# Power.net
KiCad netlist of a schematic drawn in Altium Designer
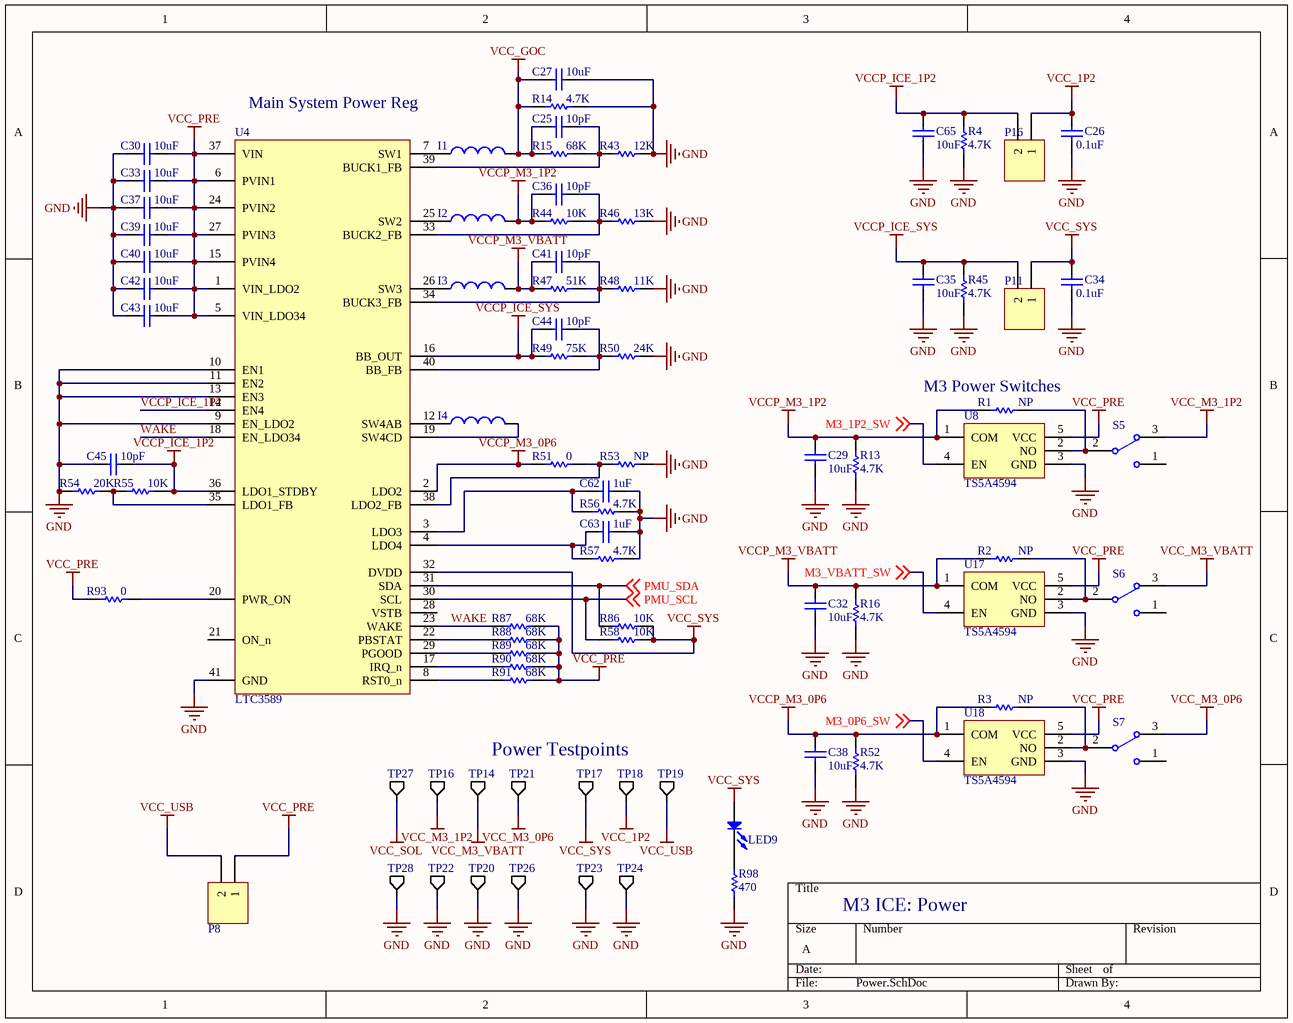
[diagram p0: Power.SchDoc]

(export (version "E")
  (design (tool "Eeschema 10.0.6"))
  (components
    (comp (ref "C25")
      (value "10pF")
      (footprint "0402")
      (description "Capacitor (Semiconductor SIM Model)")
      (fields
        (field (name "DISTPARTNO") "445-1235-1-ND")
        (field (name "MANPARTNO") "C1005C0G1H100D")
        (field (name "PUBLISHER") "Altium Limited")
      )
      (libsource (lib "Miscellaneous Devices") (part "Cap Semi"))
    )
    (comp (ref "C26")
      (value "0.1uF")
      (footprint "1608[0603]")
      (description "Capacitor (Semiconductor SIM Model)")
      (fields
        (field (name "DISTPARTNO") "1276-1005-1-ND")
        (field (name "MANPARTNO") "CL10B104KO8NNNC")
        (field (name "PUBLISHER") "Altium Limited")
      )
      (libsource (lib "Miscellaneous Devices") (part "Cap Semi"))
    )
    (comp (ref "C27")
      (value "10uF")
      (footprint "0805")
      (description "Capacitor (Semiconductor SIM Model)")
      (fields
        (field (name "DISTPARTNO") "445-6857-1-ND")
        (field (name "MANPARTNO") "C2012X7R1A106K")
        (field (name "PUBLISHER") "Altium Limited")
      )
      (libsource (lib "M3") (part "Cap Chip"))
    )
    (comp (ref "C29")
      (value "10uF")
      (footprint "0805")
      (description "Capacitor (Semiconductor SIM Model)")
      (fields
        (field (name "DISTPARTNO") "445-6857-1-ND")
        (field (name "MANPARTNO") "C2012X7R1A106K")
        (field (name "PUBLISHER") "Altium Limited")
      )
      (libsource (lib "M3") (part "Cap Chip"))
    )
    (comp (ref "C30")
      (value "10uF")
      (footprint "0805")
      (description "Capacitor (Semiconductor SIM Model)")
      (fields
        (field (name "DISTPARTNO") "445-6857-1-ND")
        (field (name "MANPARTNO") "C2012X7R1A106K")
        (field (name "PUBLISHER") "Altium Limited")
      )
      (libsource (lib "M3") (part "Cap Chip"))
    )
    (comp (ref "C32")
      (value "10uF")
      (footprint "0805")
      (description "Capacitor (Semiconductor SIM Model)")
      (fields
        (field (name "DISTPARTNO") "445-6857-1-ND")
        (field (name "MANPARTNO") "C2012X7R1A106K")
        (field (name "PUBLISHER") "Altium Limited")
      )
      (libsource (lib "M3") (part "Cap Chip"))
    )
    (comp (ref "C33")
      (value "10uF")
      (footprint "0805")
      (description "Capacitor (Semiconductor SIM Model)")
      (fields
        (field (name "DISTPARTNO") "445-6857-1-ND")
        (field (name "MANPARTNO") "C2012X7R1A106K")
        (field (name "PUBLISHER") "Altium Limited")
      )
      (libsource (lib "M3") (part "Cap Chip"))
    )
    (comp (ref "C34")
      (value "0.1uF")
      (footprint "1608[0603]")
      (description "Capacitor (Semiconductor SIM Model)")
      (fields
        (field (name "DISTPARTNO") "1276-1005-1-ND")
        (field (name "MANPARTNO") "CL10B104KO8NNNC")
        (field (name "PUBLISHER") "Altium Limited")
      )
      (libsource (lib "Miscellaneous Devices") (part "Cap Semi"))
    )
    (comp (ref "C35")
      (value "10uF")
      (footprint "0805")
      (description "Capacitor (Semiconductor SIM Model)")
      (fields
        (field (name "DISTPARTNO") "445-6857-1-ND")
        (field (name "MANPARTNO") "C2012X7R1A106K")
        (field (name "PUBLISHER") "Altium Limited")
      )
      (libsource (lib "M3") (part "Cap Chip"))
    )
    (comp (ref "C36")
      (value "10pF")
      (footprint "0402")
      (description "Capacitor (Semiconductor SIM Model)")
      (fields
        (field (name "DISTPARTNO") "445-1235-1-ND")
        (field (name "MANPARTNO") "C1005C0G1H100D")
        (field (name "PUBLISHER") "Altium Limited")
      )
      (libsource (lib "Miscellaneous Devices") (part "Cap Semi"))
    )
    (comp (ref "C37")
      (value "10uF")
      (footprint "0805")
      (description "Capacitor (Semiconductor SIM Model)")
      (fields
        (field (name "DISTPARTNO") "445-6857-1-ND")
        (field (name "MANPARTNO") "C2012X7R1A106K")
        (field (name "PUBLISHER") "Altium Limited")
      )
      (libsource (lib "M3") (part "Cap Chip"))
    )
    (comp (ref "C38")
      (value "10uF")
      (footprint "0805")
      (description "Capacitor (Semiconductor SIM Model)")
      (fields
        (field (name "DISTPARTNO") "445-6857-1-ND")
        (field (name "MANPARTNO") "C2012X7R1A106K")
        (field (name "PUBLISHER") "Altium Limited")
      )
      (libsource (lib "M3") (part "Cap Chip"))
    )
    (comp (ref "C39")
      (value "10uF")
      (footprint "0805")
      (description "Capacitor (Semiconductor SIM Model)")
      (fields
        (field (name "DISTPARTNO") "445-6857-1-ND")
        (field (name "MANPARTNO") "C2012X7R1A106K")
        (field (name "PUBLISHER") "Altium Limited")
      )
      (libsource (lib "M3") (part "Cap Chip"))
    )
    (comp (ref "C40")
      (value "10uF")
      (footprint "0805")
      (description "Capacitor (Semiconductor SIM Model)")
      (fields
        (field (name "DISTPARTNO") "445-6857-1-ND")
        (field (name "MANPARTNO") "C2012X7R1A106K")
        (field (name "PUBLISHER") "Altium Limited")
      )
      (libsource (lib "M3") (part "Cap Chip"))
    )
    (comp (ref "C41")
      (value "10pF")
      (footprint "0402")
      (description "Capacitor (Semiconductor SIM Model)")
      (fields
        (field (name "DISTPARTNO") "445-1235-1-ND")
        (field (name "MANPARTNO") "C1005C0G1H100D")
        (field (name "PUBLISHER") "Altium Limited")
      )
      (libsource (lib "Miscellaneous Devices") (part "Cap Semi"))
    )
    (comp (ref "C42")
      (value "10uF")
      (footprint "0805")
      (description "Capacitor (Semiconductor SIM Model)")
      (fields
        (field (name "DISTPARTNO") "445-6857-1-ND")
        (field (name "MANPARTNO") "C2012X7R1A106K")
        (field (name "PUBLISHER") "Altium Limited")
      )
      (libsource (lib "M3") (part "Cap Chip"))
    )
    (comp (ref "C43")
      (value "10uF")
      (footprint "0805")
      (description "Capacitor (Semiconductor SIM Model)")
      (fields
        (field (name "DISTPARTNO") "445-6857-1-ND")
        (field (name "MANPARTNO") "C2012X7R1A106K")
        (field (name "PUBLISHER") "Altium Limited")
      )
      (libsource (lib "M3") (part "Cap Chip"))
    )
    (comp (ref "C44")
      (value "10pF")
      (footprint "0402")
      (description "Capacitor (Semiconductor SIM Model)")
      (fields
        (field (name "DISTPARTNO") "445-1235-1-ND")
        (field (name "MANPARTNO") "C1005C0G1H100D")
        (field (name "PUBLISHER") "Altium Limited")
      )
      (libsource (lib "Miscellaneous Devices") (part "Cap Semi"))
    )
    (comp (ref "C45")
      (value "10pF")
      (footprint "0402")
      (description "Capacitor (Semiconductor SIM Model)")
      (fields
        (field (name "DISTPARTNO") "445-1235-1-ND")
        (field (name "MANPARTNO") "C1005C0G1H100D")
        (field (name "PUBLISHER") "Altium Limited")
      )
      (libsource (lib "Miscellaneous Devices") (part "Cap Semi"))
    )
    (comp (ref "C62")
      (value "1uF")
      (footprint "0402")
      (description "Capacitor (Semiconductor SIM Model)")
      (fields
        (field (name "DISTPARTNO") "445-4991-1-ND")
        (field (name "MANPARTNO") "C1005X5R1A105M")
        (field (name "PUBLISHER") "Altium Limited")
      )
      (libsource (lib "Miscellaneous Devices") (part "Cap Semi"))
    )
    (comp (ref "C63")
      (value "1uF")
      (footprint "0402")
      (description "Capacitor (Semiconductor SIM Model)")
      (fields
        (field (name "DISTPARTNO") "445-4991-1-ND")
        (field (name "MANPARTNO") "C1005X5R1A105M")
        (field (name "PUBLISHER") "Altium Limited")
      )
      (libsource (lib "Miscellaneous Devices") (part "Cap Semi"))
    )
    (comp (ref "C65")
      (value "10uF")
      (footprint "0805")
      (description "Capacitor (Semiconductor SIM Model)")
      (fields
        (field (name "DISTPARTNO") "445-6857-1-ND")
        (field (name "MANPARTNO") "C2012X7R1A106K")
        (field (name "PUBLISHER") "Altium Limited")
      )
      (libsource (lib "M3") (part "Cap Chip"))
    )
    (comp (ref "I1")
      (value "NR5040T1R5N")
      (footprint "INDUCTOR_.118x.142mm")
      (fields (field (name "DISTPARTNO") "541-1327-1-ND") (field (name "MANPARTNO") "IHLP1212AEER1R0M11"))
      (libsource (lib "M3") (part "IHLP1212"))
    )
    (comp (ref "I2")
      (value "NR5040T1R5N")
      (footprint "INDUCTOR_.118x.142mm")
      (fields (field (name "DISTPARTNO") "541-1327-1-ND") (field (name "MANPARTNO") "IHLP1212AEER1R0M11"))
      (libsource (lib "M3") (part "IHLP1212"))
    )
    (comp (ref "I3")
      (value "NR5040T1R5N")
      (footprint "INDUCTOR_.118x.142mm")
      (fields (field (name "DISTPARTNO") "541-1327-1-ND") (field (name "MANPARTNO") "IHLP1212AEER1R0M11"))
      (libsource (lib "M3") (part "IHLP1212"))
    )
    (comp (ref "I4")
      (value "NR5040T1R5N")
      (footprint "INDUCTOR_.118x.142mm")
      (fields (field (name "DISTPARTNO") "541-1327-1-ND") (field (name "MANPARTNO") "IHLP1212AEER1R0M11"))
      (libsource (lib "M3") (part "IHLP1212"))
    )
    (comp (ref "LED9")
      (value "LED 1206")
      (footprint "1206_LED")
      (fields (field (name "DISTPARTNO") "160-1169-1-ND") (field (name "MANPARTNO") "LTST-C150GKT"))
      (libsource (lib "M3") (part "LED 1206"))
    )
    (comp (ref "P8")
      (value "Header 2")
      (footprint "HDR1X2")
      (description "Header, 2-Pin")
      (fields
        (field (name "DISTPARTNO") "A26514-02-ND")
        (field (name "MANPARTNO") "4-103327-0-02")
        (field (name "PUBLISHER") "Altium Limited")
      )
      (libsource (lib "Miscellaneous Connectors") (part "Header 2"))
    )
    (comp (ref "P11")
      (value "Header 2")
      (footprint "HDR1X2")
      (description "Header, 2-Pin")
      (fields
        (field (name "DISTPARTNO") "A26514-02-ND")
        (field (name "MANPARTNO") "4-103327-0-02")
        (field (name "PUBLISHER") "Altium Limited")
      )
      (libsource (lib "Miscellaneous Connectors") (part "Header 2"))
    )
    (comp (ref "P16")
      (value "Header 2")
      (footprint "HDR1X2")
      (description "Header, 2-Pin")
      (fields
        (field (name "DISTPARTNO") "A26514-02-ND")
        (field (name "MANPARTNO") "4-103327-0-02")
        (field (name "PUBLISHER") "Altium Limited")
      )
      (libsource (lib "Miscellaneous Connectors") (part "Header 2"))
    )
    (comp (ref "R1")
      (value "NP")
      (footprint "0603")
      (description "Semiconductor Resistor")
      (fields (field (name "Comment") "Res Chip") (field (name "PUBLISHER") "Altium Limited"))
      (libsource (lib "M3") (part "Res Chip"))
    )
    (comp (ref "R2")
      (value "NP")
      (footprint "0603")
      (description "Semiconductor Resistor")
      (fields (field (name "Comment") "Res Chip") (field (name "PUBLISHER") "Altium Limited"))
      (libsource (lib "M3") (part "Res Chip"))
    )
    (comp (ref "R3")
      (value "NP")
      (footprint "0603")
      (description "Semiconductor Resistor")
      (fields (field (name "Comment") "Res Chip") (field (name "PUBLISHER") "Altium Limited"))
      (libsource (lib "M3") (part "Res Chip"))
    )
    (comp (ref "R4")
      (value "4.7K")
      (footprint "0603")
      (description "Semiconductor Resistor")
      (fields
        (field (name "DISTPARTNO") "P4.7KGCT-ND")
        (field (name "MANPARTNO") "ERJ-3GEYJ472V")
        (field (name "PUBLISHER") "Altium Limited")
      )
      (libsource (lib "M3") (part "Res Chip"))
    )
    (comp (ref "R13")
      (value "4.7K")
      (footprint "0603")
      (description "Semiconductor Resistor")
      (fields
        (field (name "DISTPARTNO") "P4.7KGCT-ND")
        (field (name "MANPARTNO") "ERJ-3GEYJ472V")
        (field (name "PUBLISHER") "Altium Limited")
      )
      (libsource (lib "M3") (part "Res Chip"))
    )
    (comp (ref "R14")
      (value "4.7K")
      (footprint "0603")
      (description "Semiconductor Resistor")
      (fields
        (field (name "DISTPARTNO") "P4.7KGCT-ND")
        (field (name "MANPARTNO") "ERJ-3GEYJ472V")
        (field (name "PUBLISHER") "Altium Limited")
      )
      (libsource (lib "M3") (part "Res Chip"))
    )
    (comp (ref "R15")
      (value "68K")
      (footprint "0402")
      (description "Semiconductor Resistor")
      (fields
        (field (name "DISTPARTNO") "P68.0KLCT-ND")
        (field (name "MANPARTNO") "ERJ-2RKF6802X")
        (field (name "PUBLISHER") "Altium Limited")
      )
      (libsource (lib "M3") (part "Res Chip"))
    )
    (comp (ref "R16")
      (value "4.7K")
      (footprint "0603")
      (description "Semiconductor Resistor")
      (fields
        (field (name "DISTPARTNO") "P4.7KGCT-ND")
        (field (name "MANPARTNO") "ERJ-3GEYJ472V")
        (field (name "PUBLISHER") "Altium Limited")
      )
      (libsource (lib "M3") (part "Res Chip"))
    )
    (comp (ref "R43")
      (value "12K")
      (footprint "0402")
      (description "Semiconductor Resistor")
      (fields
        (field (name "DISTPARTNO") "P12.0KLCT-ND")
        (field (name "MANPARTNO") "ERJ-2RKF1202X")
        (field (name "PUBLISHER") "Altium Limited")
      )
      (libsource (lib "M3") (part "Res Chip"))
    )
    (comp (ref "R44")
      (value "10K")
      (footprint "0402")
      (description "Semiconductor Resistor")
      (fields
        (field (name "DISTPARTNO") "P10.0KLCT-ND")
        (field (name "MANPARTNO") "ERJ-2RKF1002X")
        (field (name "PUBLISHER") "Altium Limited")
      )
      (libsource (lib "M3") (part "Res Chip"))
    )
    (comp (ref "R45")
      (value "4.7K")
      (footprint "0603")
      (description "Semiconductor Resistor")
      (fields
        (field (name "DISTPARTNO") "P4.7KGCT-ND")
        (field (name "MANPARTNO") "ERJ-3GEYJ472V")
        (field (name "PUBLISHER") "Altium Limited")
      )
      (libsource (lib "M3") (part "Res Chip"))
    )
    (comp (ref "R46")
      (value "13K")
      (footprint "0402")
      (description "Semiconductor Resistor")
      (fields
        (field (name "DISTPARTNO") "311-13.0KLRCT-ND")
        (field (name "MANPARTNO") "RC0402FR-0713KL")
        (field (name "PUBLISHER") "Altium Limited")
      )
      (libsource (lib "M3") (part "Res Chip"))
    )
    (comp (ref "R47")
      (value "51K")
      (footprint "0402")
      (description "Semiconductor Resistor")
      (fields
        (field (name "DISTPARTNO") "P51.0KLCT-ND")
        (field (name "MANPARTNO") "ERJ-2RKF5102X")
        (field (name "PUBLISHER") "Altium Limited")
      )
      (libsource (lib "M3") (part "Res Chip"))
    )
    (comp (ref "R48")
      (value "11K")
      (footprint "0402")
      (description "Semiconductor Resistor")
      (fields
        (field (name "DISTPARTNO") "P11.0KLCT-ND")
        (field (name "MANPARTNO") "ERJ-2RKF1102X")
        (field (name "PUBLISHER") "Altium Limited")
      )
      (libsource (lib "M3") (part "Res Chip"))
    )
    (comp (ref "R49")
      (value "75K")
      (footprint "0402")
      (description "Semiconductor Resistor")
      (fields
        (field (name "DISTPARTNO") "P75.0KLCT-ND")
        (field (name "MANPARTNO") "ERJ-2RKF7502X")
        (field (name "PUBLISHER") "Altium Limited")
      )
      (libsource (lib "M3") (part "Res Chip"))
    )
    (comp (ref "R50")
      (value "24K")
      (footprint "0402")
      (description "Semiconductor Resistor")
      (fields
        (field (name "DISTPARTNO") "RMCF0402FT24K0CT-ND")
        (field (name "MANPARTNO") "RMCF0402FT24K0")
        (field (name "PUBLISHER") "Altium Limited")
      )
      (libsource (lib "M3") (part "Res Chip"))
    )
    (comp (ref "R51")
      (value "0")
      (footprint "0402")
      (description "Semiconductor Resistor")
      (fields
        (field (name "DISTPARTNO") "P0.0JCT-ND")
        (field (name "MANPARTNO") "ERJ-2GE0R00X")
        (field (name "PUBLISHER") "Altium Limited")
      )
      (libsource (lib "M3") (part "Res Chip"))
    )
    (comp (ref "R52")
      (value "4.7K")
      (footprint "0603")
      (description "Semiconductor Resistor")
      (fields
        (field (name "DISTPARTNO") "P4.7KGCT-ND")
        (field (name "MANPARTNO") "ERJ-3GEYJ472V")
        (field (name "PUBLISHER") "Altium Limited")
      )
      (libsource (lib "M3") (part "Res Chip"))
    )
    (comp (ref "R53")
      (value "NP")
      (footprint "0402")
      (description "Semiconductor Resistor")
      (fields (field (name "Comment") "Res Chip") (field (name "PUBLISHER") "Altium Limited"))
      (libsource (lib "M3") (part "Res Chip"))
    )
    (comp (ref "R54")
      (value "20K")
      (footprint "0402")
      (description "Semiconductor Resistor")
      (fields
        (field (name "DISTPARTNO") "P20.0KLCT-ND")
        (field (name "MANPARTNO") "ERJ-2RKF2002X")
        (field (name "PUBLISHER") "Altium Limited")
      )
      (libsource (lib "M3") (part "Res Chip"))
    )
    (comp (ref "R55")
      (value "10K")
      (footprint "0402")
      (description "Semiconductor Resistor")
      (fields
        (field (name "DISTPARTNO") "P10.0KLCT-ND")
        (field (name "MANPARTNO") "ERJ-2RKF1002X")
        (field (name "PUBLISHER") "Altium Limited")
      )
      (libsource (lib "M3") (part "Res Chip"))
    )
    (comp (ref "R56")
      (value "4.7K")
      (footprint "0402")
      (description "Semiconductor Resistor")
      (fields
        (field (name "DISTPARTNO") "P4.70KLCT-ND")
        (field (name "MANPARTNO") "ERJ-2RKF4701X")
        (field (name "PUBLISHER") "Altium Limited")
      )
      (libsource (lib "M3") (part "Res Chip"))
    )
    (comp (ref "R57")
      (value "4.7K")
      (footprint "0402")
      (description "Semiconductor Resistor")
      (fields
        (field (name "DISTPARTNO") "P4.70KLCT-ND")
        (field (name "MANPARTNO") "ERJ-2RKF4701X")
        (field (name "PUBLISHER") "Altium Limited")
      )
      (libsource (lib "M3") (part "Res Chip"))
    )
    (comp (ref "R58")
      (value "10K")
      (footprint "0402")
      (description "Semiconductor Resistor")
      (fields
        (field (name "DISTPARTNO") "P10.0KLCT-ND")
        (field (name "MANPARTNO") "ERJ-2RKF1002X")
        (field (name "PUBLISHER") "Altium Limited")
      )
      (libsource (lib "M3") (part "Res Chip"))
    )
    (comp (ref "R86")
      (value "10K")
      (footprint "0402")
      (description "Semiconductor Resistor")
      (fields
        (field (name "DISTPARTNO") "P10.0KLCT-ND")
        (field (name "MANPARTNO") "ERJ-2RKF1002X")
        (field (name "PUBLISHER") "Altium Limited")
      )
      (libsource (lib "M3") (part "Res Chip"))
    )
    (comp (ref "R87")
      (value "68K")
      (footprint "0402")
      (description "Semiconductor Resistor")
      (fields
        (field (name "DISTPARTNO") "P68.0KLCT-ND")
        (field (name "MANPARTNO") "ERJ-2RKF6802X")
        (field (name "PUBLISHER") "Altium Limited")
      )
      (libsource (lib "M3") (part "Res Chip"))
    )
    (comp (ref "R88")
      (value "68K")
      (footprint "0402")
      (description "Semiconductor Resistor")
      (fields
        (field (name "DISTPARTNO") "P68.0KLCT-ND")
        (field (name "MANPARTNO") "ERJ-2RKF6802X")
        (field (name "PUBLISHER") "Altium Limited")
      )
      (libsource (lib "M3") (part "Res Chip"))
    )
    (comp (ref "R89")
      (value "68K")
      (footprint "0402")
      (description "Semiconductor Resistor")
      (fields
        (field (name "DISTPARTNO") "P68.0KLCT-ND")
        (field (name "MANPARTNO") "ERJ-2RKF6802X")
        (field (name "PUBLISHER") "Altium Limited")
      )
      (libsource (lib "M3") (part "Res Chip"))
    )
    (comp (ref "R90")
      (value "68K")
      (footprint "0402")
      (description "Semiconductor Resistor")
      (fields
        (field (name "DISTPARTNO") "P68.0KLCT-ND")
        (field (name "MANPARTNO") "ERJ-2RKF6802X")
        (field (name "PUBLISHER") "Altium Limited")
      )
      (libsource (lib "M3") (part "Res Chip"))
    )
    (comp (ref "R91")
      (value "68K")
      (footprint "0402")
      (description "Semiconductor Resistor")
      (fields
        (field (name "DISTPARTNO") "P68.0KLCT-ND")
        (field (name "MANPARTNO") "ERJ-2RKF6802X")
        (field (name "PUBLISHER") "Altium Limited")
      )
      (libsource (lib "M3") (part "Res Chip"))
    )
    (comp (ref "R93")
      (value "0")
      (footprint "0402")
      (description "Semiconductor Resistor")
      (fields
        (field (name "DISTPARTNO") "P0.0JCT-ND")
        (field (name "MANPARTNO") "ERJ-2GE0R00X")
        (field (name "PUBLISHER") "Altium Limited")
      )
      (libsource (lib "M3") (part "Res Chip"))
    )
    (comp (ref "R98")
      (value "470")
      (footprint "0603")
      (description "Semiconductor Resistor")
      (fields
        (field (name "DISTPARTNO") "P470GCT-ND")
        (field (name "MANPARTNO") "ERJ-3GEYJ471V")
        (field (name "PUBLISHER") "Altium Limited")
      )
      (libsource (lib "M3") (part "Res Chip"))
    )
    (comp (ref "S5")
      (value "OS102011MS2QN1")
      (footprint "SPDT_SW2")
      (description "SPDT Slide Switch")
      (fields (field (name "DISTPARTNO") "CKN9565-ND"))
      (libsource (lib "M3") (part "OS102011MS2QN1"))
    )
    (comp (ref "S6")
      (value "OS102011MS2QN1")
      (footprint "SPDT_SW2")
      (description "SPDT Slide Switch")
      (fields (field (name "DISTPARTNO") "CKN9565-ND"))
      (libsource (lib "M3") (part "OS102011MS2QN1"))
    )
    (comp (ref "S7")
      (value "OS102011MS2QN1")
      (footprint "SPDT_SW2")
      (description "SPDT Slide Switch")
      (fields (field (name "DISTPARTNO") "CKN9565-ND"))
      (libsource (lib "M3") (part "OS102011MS2QN1"))
    )
    (comp (ref "TP14") (value "TP") (footprint "TP") (libsource (lib "M3") (part "TP")))
    (comp (ref "TP16") (value "TP") (footprint "TP") (libsource (lib "M3") (part "TP")))
    (comp (ref "TP17") (value "TP") (footprint "TP") (libsource (lib "M3") (part "TP")))
    (comp (ref "TP18") (value "TP") (footprint "TP") (libsource (lib "M3") (part "TP")))
    (comp (ref "TP19") (value "TP") (footprint "TP") (libsource (lib "M3") (part "TP")))
    (comp (ref "TP20") (value "TP") (footprint "TP") (libsource (lib "M3") (part "TP")))
    (comp (ref "TP21") (value "TP") (footprint "TP") (libsource (lib "M3") (part "TP")))
    (comp (ref "TP22") (value "TP") (footprint "TP") (libsource (lib "M3") (part "TP")))
    (comp (ref "TP23") (value "TP") (footprint "TP") (libsource (lib "M3") (part "TP")))
    (comp (ref "TP24") (value "TP") (footprint "TP") (libsource (lib "M3") (part "TP")))
    (comp (ref "TP26") (value "TP") (footprint "TP") (libsource (lib "M3") (part "TP")))
    (comp (ref "TP27") (value "TP") (footprint "TP") (libsource (lib "M3") (part "TP")))
    (comp (ref "TP28") (value "TP") (footprint "TP") (libsource (lib "M3") (part "TP")))
    (comp (ref "U4")
      (value "LTC3589")
      (footprint "QFN-40")
      (fields (field (name "DISTPARTNO") "LTC3589EUJ-2#PBF-ND") (field (name "MANPARTNO") "LTC3589EUJ-2#PBF"))
      (libsource (lib "M3") (part "LTC3589"))
    )
    (comp (ref "U8")
      (value "TS5A4594")
      (footprint "SOT25")
      (description "SPST Analog Switch")
      (fields (field (name "DISTPARTNO") "296-17705-1-ND") (field (name "MANPARTNO") "TS5A4594DBVR"))
      (libsource (lib "M3") (part "TS5A4594"))
    )
    (comp (ref "U17")
      (value "TS5A4594")
      (footprint "SOT25")
      (description "SPST Analog Switch")
      (fields (field (name "DISTPARTNO") "296-17705-1-ND") (field (name "MANPARTNO") "TS5A4594DBVR"))
      (libsource (lib "M3") (part "TS5A4594"))
    )
    (comp (ref "U18")
      (value "TS5A4594")
      (footprint "SOT25")
      (description "SPST Analog Switch")
      (fields (field (name "DISTPARTNO") "296-17705-1-ND") (field (name "MANPARTNO") "TS5A4594DBVR"))
      (libsource (lib "M3") (part "TS5A4594"))
    )
  )
  (nets
    (net (code "1") (name "/WAKE") (class "Default")
      (node (ref "R87") (pin "1") (pinfunction "1_1") (pintype "passive"))
      (node (ref "U4") (pin "18") (pinfunction "EN_LDO34_18") (pintype "passive"))
      (node (ref "U4") (pin "23") (pinfunction "WAKE_23") (pintype "passive"))
    )
    (net (code "2") (name "GND") (class "Default")
      (node (ref "C26") (pin "1") (pinfunction "1_1") (pintype "passive"))
      (node (ref "C27") (pin "1") (pinfunction "1_1") (pintype "passive"))
      (node (ref "C29") (pin "1") (pinfunction "1_1") (pintype "passive"))
      (node (ref "C30") (pin "2") (pinfunction "2_2") (pintype "passive"))
      (node (ref "C32") (pin "1") (pinfunction "1_1") (pintype "passive"))
      (node (ref "C33") (pin "2") (pinfunction "2_2") (pintype "passive"))
      (node (ref "C34") (pin "1") (pinfunction "1_1") (pintype "passive"))
      (node (ref "C35") (pin "1") (pinfunction "1_1") (pintype "passive"))
      (node (ref "C37") (pin "2") (pinfunction "2_2") (pintype "passive"))
      (node (ref "C38") (pin "1") (pinfunction "1_1") (pintype "passive"))
      (node (ref "C39") (pin "2") (pinfunction "2_2") (pintype "passive"))
      (node (ref "C40") (pin "2") (pinfunction "2_2") (pintype "passive"))
      (node (ref "C42") (pin "2") (pinfunction "2_2") (pintype "passive"))
      (node (ref "C43") (pin "2") (pinfunction "2_2") (pintype "passive"))
      (node (ref "C45") (pin "2") (pinfunction "2_2") (pintype "passive"))
      (node (ref "C62") (pin "1") (pinfunction "1_1") (pintype "passive"))
      (node (ref "C63") (pin "1") (pinfunction "1_1") (pintype "passive"))
      (node (ref "C65") (pin "2") (pinfunction "2_2") (pintype "passive"))
      (node (ref "R13") (pin "1") (pinfunction "1_1") (pintype "passive"))
      (node (ref "R14") (pin "1") (pinfunction "1_1") (pintype "passive"))
      (node (ref "R16") (pin "1") (pinfunction "1_1") (pintype "passive"))
      (node (ref "R4") (pin "2") (pinfunction "2_2") (pintype "passive"))
      (node (ref "R43") (pin "2") (pinfunction "2_2") (pintype "passive"))
      (node (ref "R45") (pin "1") (pinfunction "1_1") (pintype "passive"))
      (node (ref "R46") (pin "2") (pinfunction "2_2") (pintype "passive"))
      (node (ref "R48") (pin "2") (pinfunction "2_2") (pintype "passive"))
      (node (ref "R50") (pin "2") (pinfunction "2_2") (pintype "passive"))
      (node (ref "R52") (pin "1") (pinfunction "1_1") (pintype "passive"))
      (node (ref "R53") (pin "2") (pinfunction "2_2") (pintype "passive"))
      (node (ref "R54") (pin "1") (pinfunction "1_1") (pintype "passive"))
      (node (ref "R56") (pin "2") (pinfunction "2_2") (pintype "passive"))
      (node (ref "R57") (pin "2") (pinfunction "2_2") (pintype "passive"))
      (node (ref "R98") (pin "1") (pinfunction "1_1") (pintype "passive"))
      (node (ref "TP20") (pin "1") (pinfunction "A_1") (pintype "passive"))
      (node (ref "TP22") (pin "1") (pinfunction "A_1") (pintype "passive"))
      (node (ref "TP23") (pin "1") (pinfunction "A_1") (pintype "passive"))
      (node (ref "TP24") (pin "1") (pinfunction "A_1") (pintype "passive"))
      (node (ref "TP26") (pin "1") (pinfunction "A_1") (pintype "passive"))
      (node (ref "TP28") (pin "1") (pinfunction "A_1") (pintype "passive"))
      (node (ref "U17") (pin "3") (pinfunction "GND_3") (pintype "passive"))
      (node (ref "U18") (pin "3") (pinfunction "GND_3") (pintype "passive"))
      (node (ref "U4") (pin "10") (pinfunction "EN1_10") (pintype "passive"))
      (node (ref "U4") (pin "11") (pinfunction "EN2_11") (pintype "passive"))
      (node (ref "U4") (pin "13") (pinfunction "EN3_13") (pintype "passive"))
      (node (ref "U4") (pin "41") (pinfunction "GND_41") (pintype "passive"))
      (node (ref "U4") (pin "9") (pinfunction "EN_LDO2_9") (pintype "passive"))
      (node (ref "U8") (pin "3") (pinfunction "GND_3") (pintype "passive"))
    )
    (net (code "3") (name "M3_0P6_SW") (class "Default")
      (node (ref "U18") (pin "4") (pinfunction "EN_4") (pintype "passive"))
    )
    (net (code "4") (name "M3_1P2_SW") (class "Default")
      (node (ref "U8") (pin "4") (pinfunction "EN_4") (pintype "passive"))
    )
    (net (code "5") (name "M3_VBATT_SW") (class "Default")
      (node (ref "U17") (pin "4") (pinfunction "EN_4") (pintype "passive"))
    )
    (net (code "6") (name "Net-(LED9-K)") (class "Default")
      (node (ref "LED9") (pin "2") (pinfunction "K_2") (pintype "passive"))
      (node (ref "R98") (pin "2") (pinfunction "2_2") (pintype "passive"))
    )
    (net (code "7") (name "Net-(U4-BB_FB)") (class "Default")
      (node (ref "C44") (pin "1") (pinfunction "1_1") (pintype "passive"))
      (node (ref "R49") (pin "2") (pinfunction "2_2") (pintype "passive"))
      (node (ref "R50") (pin "1") (pinfunction "1_1") (pintype "passive"))
      (node (ref "U4") (pin "40") (pinfunction "BB_FB_40") (pintype "passive"))
    )
    (net (code "8") (name "Net-(U4-BUCK1_FB)") (class "Default")
      (node (ref "C25") (pin "1") (pinfunction "1_1") (pintype "passive"))
      (node (ref "R15") (pin "2") (pinfunction "2_2") (pintype "passive"))
      (node (ref "R43") (pin "1") (pinfunction "1_1") (pintype "passive"))
      (node (ref "U4") (pin "39") (pinfunction "BUCK1_FB_39") (pintype "passive"))
    )
    (net (code "9") (name "Net-(U4-BUCK2_FB)") (class "Default")
      (node (ref "C36") (pin "1") (pinfunction "1_1") (pintype "passive"))
      (node (ref "R44") (pin "2") (pinfunction "2_2") (pintype "passive"))
      (node (ref "R46") (pin "1") (pinfunction "1_1") (pintype "passive"))
      (node (ref "U4") (pin "33") (pinfunction "BUCK2_FB_33") (pintype "passive"))
    )
    (net (code "10") (name "Net-(U4-BUCK3_FB)") (class "Default")
      (node (ref "C41") (pin "1") (pinfunction "1_1") (pintype "passive"))
      (node (ref "R47") (pin "2") (pinfunction "2_2") (pintype "passive"))
      (node (ref "R48") (pin "1") (pinfunction "1_1") (pintype "passive"))
      (node (ref "U4") (pin "34") (pinfunction "BUCK3_FB_34") (pintype "passive"))
    )
    (net (code "11") (name "Net-(U4-IRQ_n)") (class "Default")
      (node (ref "R90") (pin "1") (pinfunction "1_1") (pintype "passive"))
      (node (ref "U4") (pin "17") (pinfunction "IRQ_n_17") (pintype "passive"))
    )
    (net (code "12") (name "Net-(U4-LDO1_FB)") (class "Default")
      (node (ref "R54") (pin "2") (pinfunction "2_2") (pintype "passive"))
      (node (ref "R55") (pin "1") (pinfunction "1_1") (pintype "passive"))
      (node (ref "U4") (pin "35") (pinfunction "LDO1_FB_35") (pintype "passive"))
    )
    (net (code "13") (name "Net-(U4-LDO2_FB)") (class "Default")
      (node (ref "R51") (pin "2") (pinfunction "2_2") (pintype "passive"))
      (node (ref "R53") (pin "1") (pinfunction "1_1") (pintype "passive"))
      (node (ref "U4") (pin "38") (pinfunction "LDO2_FB_38") (pintype "passive"))
    )
    (net (code "14") (name "Net-(U4-LDO3)") (class "Default")
      (node (ref "C62") (pin "2") (pinfunction "2_2") (pintype "passive"))
      (node (ref "R56") (pin "1") (pinfunction "1_1") (pintype "passive"))
      (node (ref "U4") (pin "3") (pinfunction "LDO3_3") (pintype "passive"))
    )
    (net (code "15") (name "Net-(U4-LDO4)") (class "Default")
      (node (ref "C63") (pin "2") (pinfunction "2_2") (pintype "passive"))
      (node (ref "R57") (pin "1") (pinfunction "1_1") (pintype "passive"))
      (node (ref "U4") (pin "4") (pinfunction "LDO4_4") (pintype "passive"))
    )
    (net (code "16") (name "Net-(U4-PBSTAT)") (class "Default")
      (node (ref "R88") (pin "1") (pinfunction "1_1") (pintype "passive"))
      (node (ref "U4") (pin "22") (pinfunction "PBSTAT_22") (pintype "passive"))
    )
    (net (code "17") (name "Net-(U4-PGOOD)") (class "Default")
      (node (ref "R89") (pin "1") (pinfunction "1_1") (pintype "passive"))
      (node (ref "U4") (pin "29") (pinfunction "PGOOD_29") (pintype "passive"))
    )
    (net (code "18") (name "Net-(U4-PWR_ON)") (class "Default")
      (node (ref "R93") (pin "2") (pinfunction "2_2") (pintype "passive"))
      (node (ref "U4") (pin "20") (pinfunction "PWR_ON_20") (pintype "passive"))
    )
    (net (code "19") (name "Net-(U4-RST0_n)") (class "Default")
      (node (ref "R91") (pin "1") (pinfunction "1_1") (pintype "passive"))
      (node (ref "U4") (pin "8") (pinfunction "RST0_n_8") (pintype "passive"))
    )
    (net (code "20") (name "Net-(U4-SW1)") (class "Default")
      (node (ref "I1") (pin "1") (pinfunction "1_1") (pintype "passive"))
      (node (ref "U4") (pin "7") (pinfunction "SW1_7") (pintype "passive"))
    )
    (net (code "21") (name "Net-(U4-SW2)") (class "Default")
      (node (ref "I2") (pin "1") (pinfunction "1_1") (pintype "passive"))
      (node (ref "U4") (pin "25") (pinfunction "SW2_25") (pintype "passive"))
    )
    (net (code "22") (name "Net-(U4-SW3)") (class "Default")
      (node (ref "I3") (pin "1") (pinfunction "1_1") (pintype "passive"))
      (node (ref "U4") (pin "26") (pinfunction "SW3_26") (pintype "passive"))
    )
    (net (code "23") (name "Net-(U4-SW4AB)") (class "Default")
      (node (ref "I4") (pin "1") (pinfunction "1_1") (pintype "passive"))
      (node (ref "U4") (pin "12") (pinfunction "SW4AB_12") (pintype "passive"))
    )
    (net (code "24") (name "Net-(U4-SW4CD)") (class "Default")
      (node (ref "I4") (pin "2") (pinfunction "2_2") (pintype "passive"))
      (node (ref "U4") (pin "19") (pinfunction "SW4CD_19") (pintype "passive"))
    )
    (net (code "25") (name "Net-(U8-NO)") (class "Default")
      (node (ref "R1") (pin "1") (pinfunction "1_1") (pintype "passive"))
      (node (ref "S5") (pin "2") (pinfunction "2_2") (pintype "passive"))
      (node (ref "U8") (pin "2") (pinfunction "NO_2") (pintype "passive"))
    )
    (net (code "26") (name "Net-(U17-NO)") (class "Default")
      (node (ref "R2") (pin "1") (pinfunction "1_1") (pintype "passive"))
      (node (ref "S6") (pin "2") (pinfunction "2_2") (pintype "passive"))
      (node (ref "U17") (pin "2") (pinfunction "NO_2") (pintype "passive"))
    )
    (net (code "27") (name "Net-(U18-NO)") (class "Default")
      (node (ref "R3") (pin "1") (pinfunction "1_1") (pintype "passive"))
      (node (ref "S7") (pin "2") (pinfunction "2_2") (pintype "passive"))
      (node (ref "U18") (pin "2") (pinfunction "NO_2") (pintype "passive"))
    )
    (net (code "28") (name "PMU_SCL") (class "Default")
      (node (ref "R58") (pin "1") (pinfunction "1_1") (pintype "passive"))
      (node (ref "U4") (pin "30") (pinfunction "SCL_30") (pintype "passive"))
    )
    (net (code "29") (name "PMU_SDA") (class "Default")
      (node (ref "R86") (pin "1") (pinfunction "1_1") (pintype "passive"))
      (node (ref "U4") (pin "31") (pinfunction "SDA_31") (pintype "passive"))
    )
    (net (code "30") (name "VCCP_ICE_1P2") (class "Default")
      (node (ref "C45") (pin "1") (pinfunction "1_1") (pintype "passive"))
      (node (ref "C65") (pin "1") (pinfunction "1_1") (pintype "passive"))
      (node (ref "P16") (pin "2") (pinfunction "2_2") (pintype "passive"))
      (node (ref "R4") (pin "1") (pinfunction "1_1") (pintype "passive"))
      (node (ref "R55") (pin "2") (pinfunction "2_2") (pintype "passive"))
      (node (ref "U4") (pin "14") (pinfunction "EN4_14") (pintype "passive"))
      (node (ref "U4") (pin "36") (pinfunction "LDO1_STDBY_36") (pintype "passive"))
    )
    (net (code "31") (name "VCCP_ICE_SYS") (class "Default")
      (node (ref "C35") (pin "2") (pinfunction "2_2") (pintype "passive"))
      (node (ref "C44") (pin "2") (pinfunction "2_2") (pintype "passive"))
      (node (ref "P11") (pin "2") (pinfunction "2_2") (pintype "passive"))
      (node (ref "R45") (pin "2") (pinfunction "2_2") (pintype "passive"))
      (node (ref "R49") (pin "1") (pinfunction "1_1") (pintype "passive"))
      (node (ref "U4") (pin "16") (pinfunction "BB_OUT_16") (pintype "passive"))
    )
    (net (code "32") (name "VCCP_M3_0P6") (class "Default")
      (node (ref "C38") (pin "2") (pinfunction "2_2") (pintype "passive"))
      (node (ref "R3") (pin "2") (pinfunction "2_2") (pintype "passive"))
      (node (ref "R51") (pin "1") (pinfunction "1_1") (pintype "passive"))
      (node (ref "R52") (pin "2") (pinfunction "2_2") (pintype "passive"))
      (node (ref "U18") (pin "1") (pinfunction "COM_1") (pintype "passive"))
      (node (ref "U4") (pin "2") (pinfunction "LDO2_2") (pintype "passive"))
    )
    (net (code "33") (name "VCCP_M3_1P2") (class "Default")
      (node (ref "C29") (pin "2") (pinfunction "2_2") (pintype "passive"))
      (node (ref "C36") (pin "2") (pinfunction "2_2") (pintype "passive"))
      (node (ref "I2") (pin "2") (pinfunction "2_2") (pintype "passive"))
      (node (ref "R1") (pin "2") (pinfunction "2_2") (pintype "passive"))
      (node (ref "R13") (pin "2") (pinfunction "2_2") (pintype "passive"))
      (node (ref "R44") (pin "1") (pinfunction "1_1") (pintype "passive"))
      (node (ref "U8") (pin "1") (pinfunction "COM_1") (pintype "passive"))
    )
    (net (code "34") (name "VCCP_M3_VBATT") (class "Default")
      (node (ref "C32") (pin "2") (pinfunction "2_2") (pintype "passive"))
      (node (ref "C41") (pin "2") (pinfunction "2_2") (pintype "passive"))
      (node (ref "I3") (pin "2") (pinfunction "2_2") (pintype "passive"))
      (node (ref "R16") (pin "2") (pinfunction "2_2") (pintype "passive"))
      (node (ref "R2") (pin "2") (pinfunction "2_2") (pintype "passive"))
      (node (ref "R47") (pin "1") (pinfunction "1_1") (pintype "passive"))
      (node (ref "U17") (pin "1") (pinfunction "COM_1") (pintype "passive"))
    )
    (net (code "35") (name "VCC_1P2") (class "Default")
      (node (ref "C26") (pin "2") (pinfunction "2_2") (pintype "passive"))
      (node (ref "P16") (pin "1") (pinfunction "1_1") (pintype "passive"))
      (node (ref "TP18") (pin "1") (pinfunction "A_1") (pintype "passive"))
    )
    (net (code "36") (name "VCC_GOC") (class "Default")
      (node (ref "C25") (pin "2") (pinfunction "2_2") (pintype "passive"))
      (node (ref "C27") (pin "2") (pinfunction "2_2") (pintype "passive"))
      (node (ref "I1") (pin "2") (pinfunction "2_2") (pintype "passive"))
      (node (ref "R14") (pin "2") (pinfunction "2_2") (pintype "passive"))
      (node (ref "R15") (pin "1") (pinfunction "1_1") (pintype "passive"))
    )
    (net (code "37") (name "VCC_M3_0P6") (class "Default")
      (node (ref "S7") (pin "3") (pinfunction "3_3") (pintype "passive"))
      (node (ref "TP21") (pin "1") (pinfunction "A_1") (pintype "passive"))
    )
    (net (code "38") (name "VCC_M3_1P2") (class "Default")
      (node (ref "S5") (pin "3") (pinfunction "3_3") (pintype "passive"))
      (node (ref "TP16") (pin "1") (pinfunction "A_1") (pintype "passive"))
    )
    (net (code "39") (name "VCC_M3_VBATT") (class "Default")
      (node (ref "S6") (pin "3") (pinfunction "3_3") (pintype "passive"))
      (node (ref "TP14") (pin "1") (pinfunction "A_1") (pintype "passive"))
    )
    (net (code "40") (name "VCC_PRE") (class "Default")
      (node (ref "C30") (pin "1") (pinfunction "1_1") (pintype "passive"))
      (node (ref "C33") (pin "1") (pinfunction "1_1") (pintype "passive"))
      (node (ref "C37") (pin "1") (pinfunction "1_1") (pintype "passive"))
      (node (ref "C39") (pin "1") (pinfunction "1_1") (pintype "passive"))
      (node (ref "C40") (pin "1") (pinfunction "1_1") (pintype "passive"))
      (node (ref "C42") (pin "1") (pinfunction "1_1") (pintype "passive"))
      (node (ref "C43") (pin "1") (pinfunction "1_1") (pintype "passive"))
      (node (ref "P8") (pin "1") (pinfunction "1_1") (pintype "passive"))
      (node (ref "R87") (pin "2") (pinfunction "2_2") (pintype "passive"))
      (node (ref "R88") (pin "2") (pinfunction "2_2") (pintype "passive"))
      (node (ref "R89") (pin "2") (pinfunction "2_2") (pintype "passive"))
      (node (ref "R90") (pin "2") (pinfunction "2_2") (pintype "passive"))
      (node (ref "R91") (pin "2") (pinfunction "2_2") (pintype "passive"))
      (node (ref "R93") (pin "1") (pinfunction "1_1") (pintype "passive"))
      (node (ref "U17") (pin "5") (pinfunction "VCC_5") (pintype "passive"))
      (node (ref "U18") (pin "5") (pinfunction "VCC_5") (pintype "passive"))
      (node (ref "U4") (pin "1") (pinfunction "VIN_LDO2_1") (pintype "passive"))
      (node (ref "U4") (pin "15") (pinfunction "PVIN4_15") (pintype "passive"))
      (node (ref "U4") (pin "24") (pinfunction "PVIN2_24") (pintype "passive"))
      (node (ref "U4") (pin "27") (pinfunction "PVIN3_27") (pintype "passive"))
      (node (ref "U4") (pin "37") (pinfunction "VIN_37") (pintype "passive"))
      (node (ref "U4") (pin "5") (pinfunction "VIN_LDO34_5") (pintype "passive"))
      (node (ref "U4") (pin "6") (pinfunction "PVIN1_6") (pintype "passive"))
      (node (ref "U8") (pin "5") (pinfunction "VCC_5") (pintype "passive"))
    )
    (net (code "41") (name "VCC_SOL") (class "Default")
      (node (ref "TP27") (pin "1") (pinfunction "A_1") (pintype "passive"))
    )
    (net (code "42") (name "VCC_SYS") (class "Default")
      (node (ref "C34") (pin "2") (pinfunction "2_2") (pintype "passive"))
      (node (ref "LED9") (pin "1") (pinfunction "A_1") (pintype "passive"))
      (node (ref "P11") (pin "1") (pinfunction "1_1") (pintype "passive"))
      (node (ref "R58") (pin "2") (pinfunction "2_2") (pintype "passive"))
      (node (ref "R86") (pin "2") (pinfunction "2_2") (pintype "passive"))
      (node (ref "TP17") (pin "1") (pinfunction "A_1") (pintype "passive"))
      (node (ref "U4") (pin "32") (pinfunction "DVDD_32") (pintype "passive"))
    )
    (net (code "43") (name "VCC_USB") (class "Default")
      (node (ref "P8") (pin "2") (pinfunction "2_2") (pintype "passive"))
      (node (ref "TP19") (pin "1") (pinfunction "A_1") (pintype "passive"))
    )
    (net (code "44") (name "unconnected-(S5-Pad1)") (class "Default")
      (node (ref "S5") (pin "1") (pinfunction "1_1") (pintype "passive"))
    )
    (net (code "45") (name "unconnected-(S6-Pad1)") (class "Default")
      (node (ref "S6") (pin "1") (pinfunction "1_1") (pintype "passive"))
    )
    (net (code "46") (name "unconnected-(S7-Pad1)") (class "Default")
      (node (ref "S7") (pin "1") (pinfunction "1_1") (pintype "passive"))
    )
    (net (code "47") (name "unconnected-(U4-ON_n-Pad21)") (class "Default")
      (node (ref "U4") (pin "21") (pinfunction "ON_n_21") (pintype "passive"))
    )
    (net (code "48") (name "unconnected-(U4-VSTB-Pad28)") (class "Default")
      (node (ref "U4") (pin "28") (pinfunction "VSTB_28") (pintype "passive"))
    )
  )
)
